# Temperature.net
KiCad netlist of a schematic drawn in Altium Designer
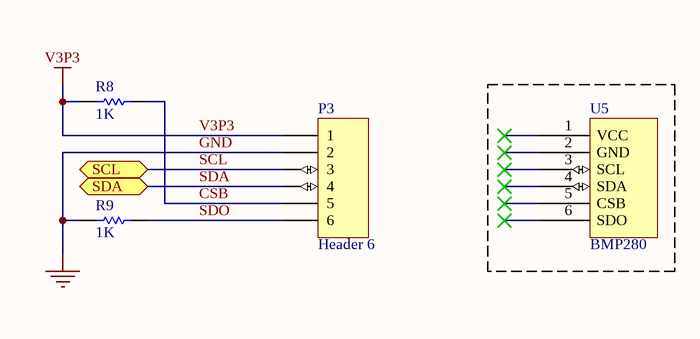
[diagram p0: Temperature.SchDoc]

(export (version "E")
  (design (tool "Eeschema 10.0.6"))
  (components
    (comp (ref "P3")
      (value "Header 6")
      (footprint "Header 6")
      (description "Header, 6-Pin")
      (libsource (lib "Miscellaneous Connectors") (part "Header 6"))
    )
    (comp (ref "R8")
      (value "1K")
      (footprint "RES0603")
      (description "Resistor")
      (fields (field (name "PUBLISHER") "Altium Limited"))
      (libsource (lib "Miscellaneous Devices") (part "Res1"))
    )
    (comp (ref "R9")
      (value "1K")
      (footprint "RES0603")
      (description "Resistor")
      (fields (field (name "PUBLISHER") "Altium Limited"))
      (libsource (lib "Miscellaneous Devices") (part "Res1"))
    )
    (comp (ref "U5")
      (value "BMP280")
      (description "Temp. sensor")
      (libsource (lib "Components") (part "BMP280"))
    )
  )
  (nets
    (net (code "1") (name "/CSB") (class "Default")
      (node (ref "P3") (pin "5") (pinfunction "5_5") (pintype "passive"))
      (node (ref "R8") (pin "2") (pinfunction "2_2") (pintype "passive"))
    )
    (net (code "2") (name "/SCL") (class "Default")
      (node (ref "P3") (pin "3") (pinfunction "3_3") (pintype "bidirectional"))
    )
    (net (code "3") (name "/SDA") (class "Default")
      (node (ref "P3") (pin "4") (pinfunction "4_4") (pintype "bidirectional"))
    )
    (net (code "4") (name "/SDO") (class "Default")
      (node (ref "P3") (pin "6") (pinfunction "6_6") (pintype "passive"))
      (node (ref "R9") (pin "2") (pinfunction "2_2") (pintype "passive"))
    )
    (net (code "5") (name "GND") (class "Default")
      (node (ref "P3") (pin "2") (pinfunction "2_2") (pintype "power_in"))
      (node (ref "R9") (pin "1") (pinfunction "1_1") (pintype "passive"))
    )
    (net (code "6") (name "V3P3") (class "Default")
      (node (ref "P3") (pin "1") (pinfunction "1_1") (pintype "power_in"))
      (node (ref "R8") (pin "1") (pinfunction "1_1") (pintype "passive"))
    )
    (net (code "7") (name "unconnected-(U5-CSB-Pad5)") (class "Default")
      (node (ref "U5") (pin "5") (pinfunction "CSB_5") (pintype "passive+no_connect"))
    )
    (net (code "8") (name "unconnected-(U5-GND-Pad2)") (class "Default")
      (node (ref "U5") (pin "2") (pinfunction "GND_2") (pintype "power_in+no_connect"))
    )
    (net (code "9") (name "unconnected-(U5-SCL-Pad3)") (class "Default")
      (node (ref "U5") (pin "3") (pinfunction "SCL_3") (pintype "bidirectional+no_connect"))
    )
    (net (code "10") (name "unconnected-(U5-SDA-Pad4)") (class "Default")
      (node (ref "U5") (pin "4") (pinfunction "SDA_4") (pintype "bidirectional+no_connect"))
    )
    (net (code "11") (name "unconnected-(U5-SDO-Pad6)") (class "Default")
      (node (ref "U5") (pin "6") (pinfunction "SDO_6") (pintype "passive+no_connect"))
    )
    (net (code "12") (name "unconnected-(U5-VCC-Pad1)") (class "Default")
      (node (ref "U5") (pin "1") (pinfunction "VCC_1") (pintype "power_in+no_connect"))
    )
  )
)
